# design.net
KiCad netlist of a schematic drawn in Altium Designer
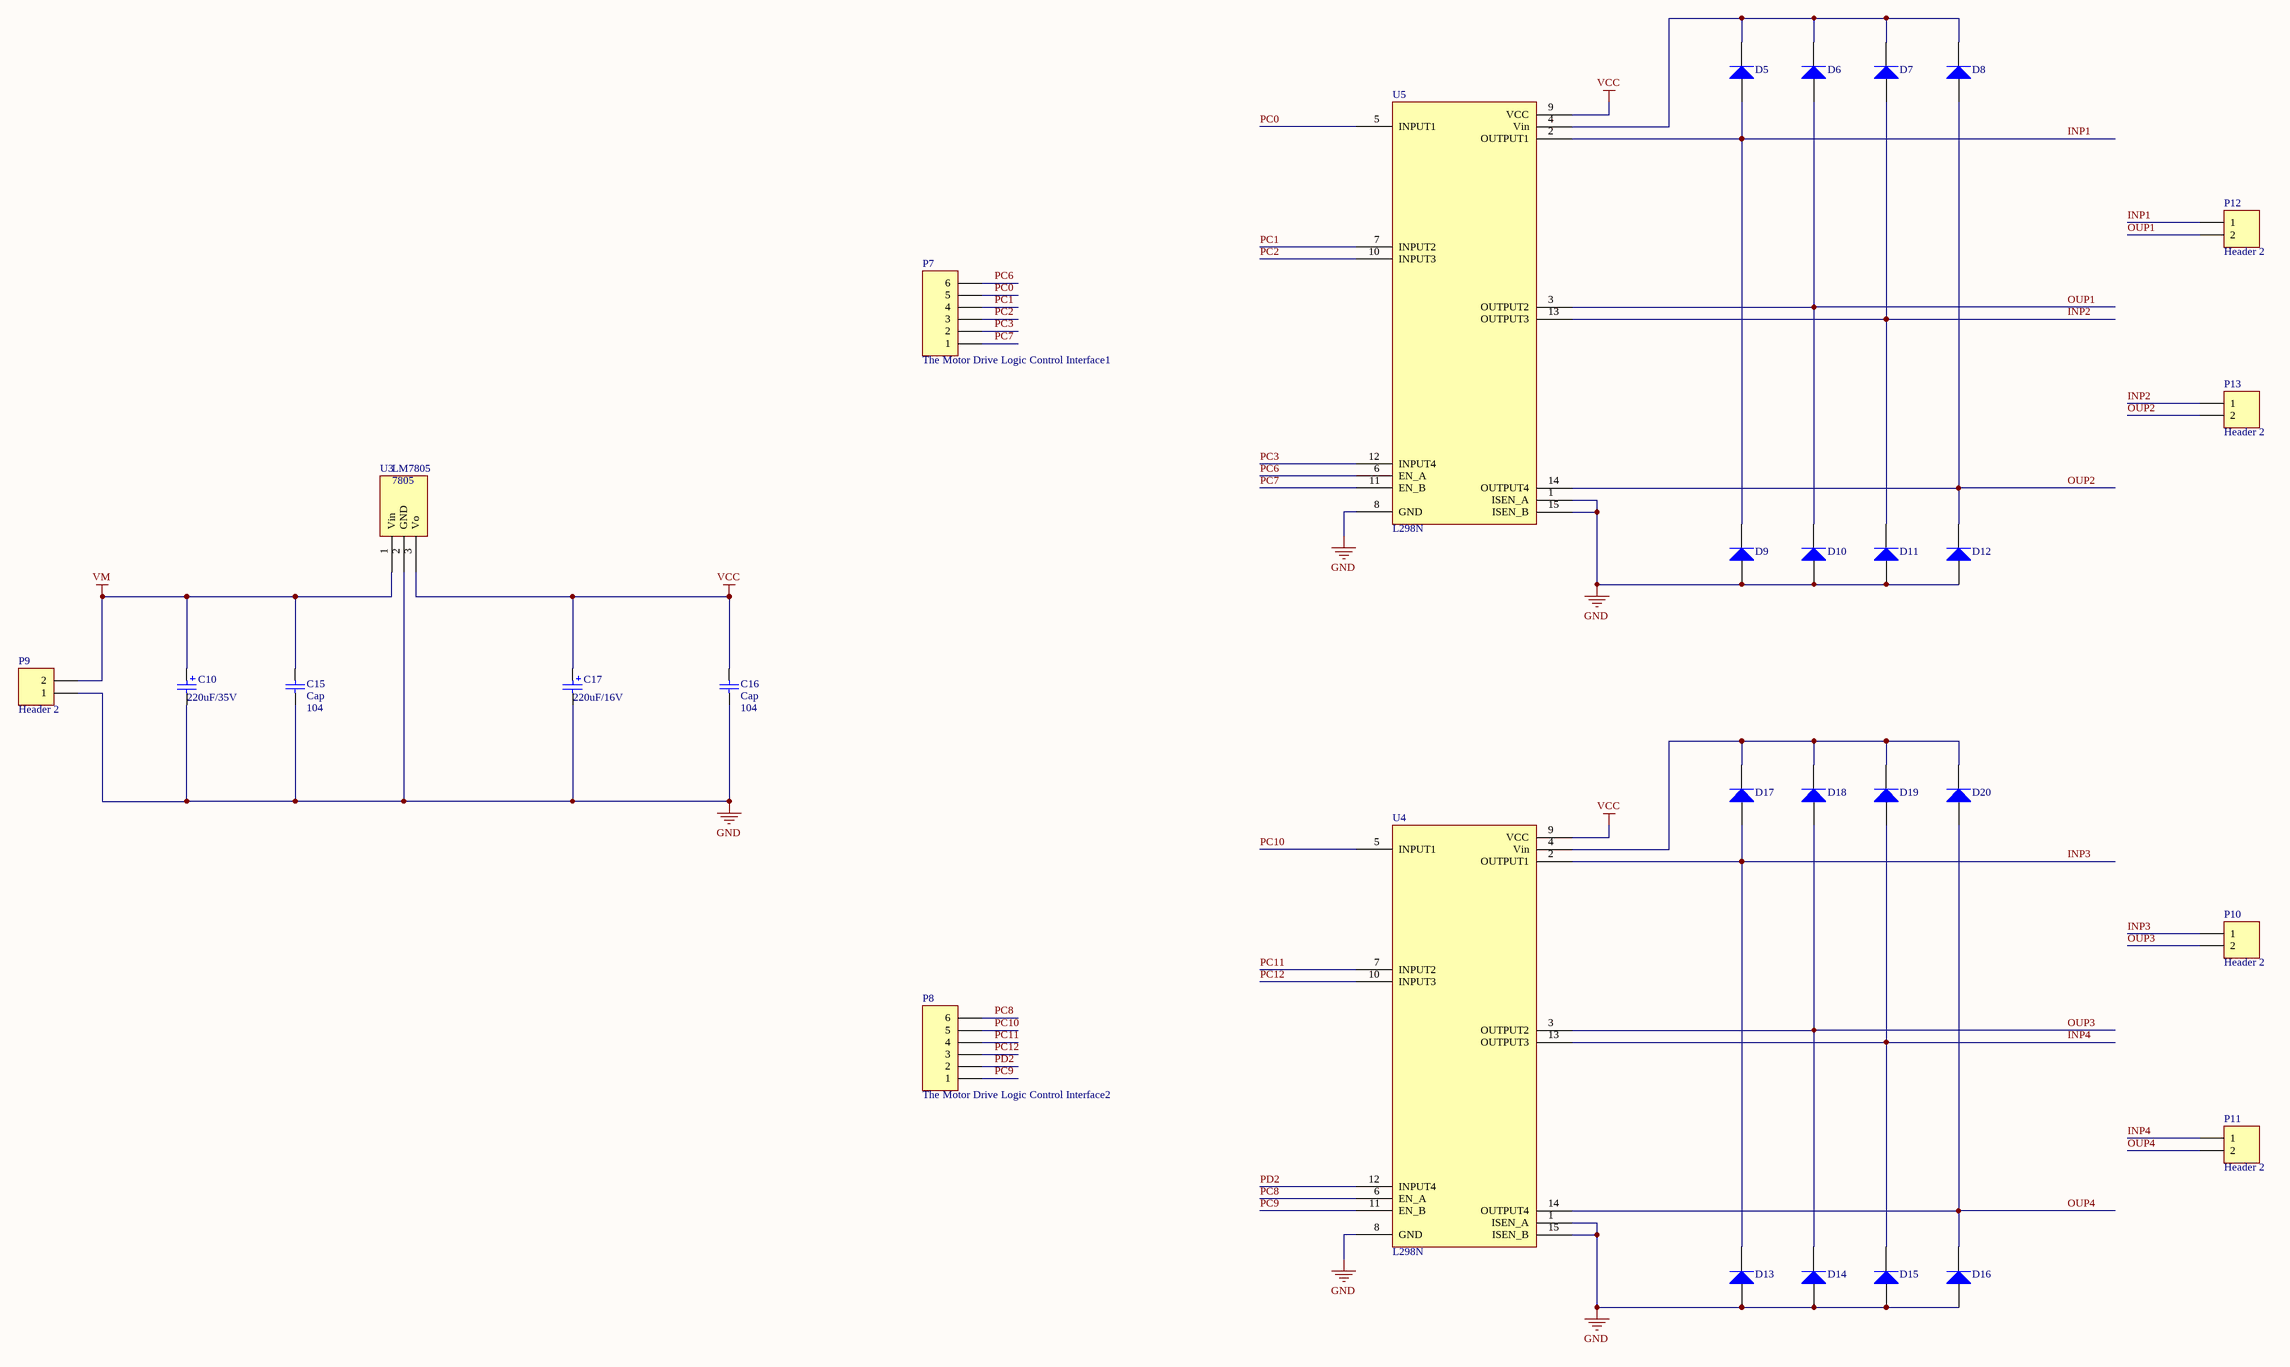
[diagram p0: 嵌入式驱动模块.SchDoc]

(export (version "E")
  (design (tool "Eeschema 10.0.6"))
  (components
    (comp (ref "C10")
      (value "220uF/35V")
      (footprint "RB 5/10")
      (description "Polarized Capacitor (Axial)")
      (fields (field (name "Comment") "Cap Pol2") (field (name "PUBLISHER") "Altium Limited"))
      (libsource (lib "Miscellaneous Devices") (part "Cap Pol2"))
    )
    (comp (ref "C15")
      (value "Cap")
      (footprint "CAP-0.1")
      (description "Capacitor")
      (fields (field (name "ALTIUM_VALUE") "104") (field (name "PUBLISHER") "Altium Limited"))
      (libsource (lib "Miscellaneous Devices") (part "Cap"))
    )
    (comp (ref "C16")
      (value "Cap")
      (footprint "CAP-0.1")
      (description "Capacitor")
      (fields (field (name "ALTIUM_VALUE") "104") (field (name "PUBLISHER") "Altium Limited"))
      (libsource (lib "Miscellaneous Devices") (part "Cap"))
    )
    (comp (ref "C17")
      (value "220uF/16V")
      (footprint "RB 5/10")
      (description "Polarized Capacitor (Axial)")
      (fields (field (name "Comment") "Cap Pol2") (field (name "PUBLISHER") "Altium Limited"))
      (libsource (lib "Miscellaneous Devices") (part "Cap Pol2"))
    )
    (comp (ref "D5")
      (value "~")
      (footprint "DO-41")
      (description "High Conductance Fast Diode")
      (fields (field (name "PUBLISHER") "Altium Limited"))
      (libsource (lib "Miscellaneous Devices") (part "Diode 1N914"))
    )
    (comp (ref "D6")
      (value "Diode 1N914")
      (footprint "DO-41")
      (description "High Conductance Fast Diode")
      (fields (field (name "PUBLISHER") "Altium Limited"))
      (libsource (lib "Miscellaneous Devices") (part "Diode 1N914"))
    )
    (comp (ref "D7")
      (value "Diode 1N914")
      (footprint "DO-41")
      (description "High Conductance Fast Diode")
      (fields (field (name "PUBLISHER") "Altium Limited"))
      (libsource (lib "Miscellaneous Devices") (part "Diode 1N914"))
    )
    (comp (ref "D8")
      (value "~")
      (footprint "DO-41")
      (description "High Conductance Fast Diode")
      (fields (field (name "PUBLISHER") "Altium Limited"))
      (libsource (lib "Miscellaneous Devices") (part "Diode 1N914"))
    )
    (comp (ref "D9")
      (value "Diode 1N914")
      (footprint "DO-41")
      (description "High Conductance Fast Diode")
      (fields (field (name "PUBLISHER") "Altium Limited"))
      (libsource (lib "Miscellaneous Devices") (part "Diode 1N914"))
    )
    (comp (ref "D10")
      (value "Diode 1N914")
      (footprint "DO-41")
      (description "High Conductance Fast Diode")
      (fields (field (name "PUBLISHER") "Altium Limited"))
      (libsource (lib "Miscellaneous Devices") (part "Diode 1N914"))
    )
    (comp (ref "D11")
      (value "Diode 1N914")
      (footprint "DO-41")
      (description "High Conductance Fast Diode")
      (fields (field (name "PUBLISHER") "Altium Limited"))
      (libsource (lib "Miscellaneous Devices") (part "Diode 1N914"))
    )
    (comp (ref "D12")
      (value "Diode 1N914")
      (footprint "DO-41")
      (description "High Conductance Fast Diode")
      (fields (field (name "PUBLISHER") "Altium Limited"))
      (libsource (lib "Miscellaneous Devices") (part "Diode 1N914"))
    )
    (comp (ref "D13")
      (value "Diode 1N914")
      (footprint "DO-41")
      (description "High Conductance Fast Diode")
      (fields (field (name "PUBLISHER") "Altium Limited"))
      (libsource (lib "Miscellaneous Devices") (part "Diode 1N914"))
    )
    (comp (ref "D14")
      (value "Diode 1N914")
      (footprint "DO-41")
      (description "High Conductance Fast Diode")
      (fields (field (name "PUBLISHER") "Altium Limited"))
      (libsource (lib "Miscellaneous Devices") (part "Diode 1N914"))
    )
    (comp (ref "D15")
      (value "Diode 1N914")
      (footprint "DO-41")
      (description "High Conductance Fast Diode")
      (fields (field (name "PUBLISHER") "Altium Limited"))
      (libsource (lib "Miscellaneous Devices") (part "Diode 1N914"))
    )
    (comp (ref "D16")
      (value "Diode 1N914")
      (footprint "DO-41")
      (description "High Conductance Fast Diode")
      (fields (field (name "PUBLISHER") "Altium Limited"))
      (libsource (lib "Miscellaneous Devices") (part "Diode 1N914"))
    )
    (comp (ref "D17")
      (value "~")
      (footprint "DO-41")
      (description "High Conductance Fast Diode")
      (fields (field (name "PUBLISHER") "Altium Limited"))
      (libsource (lib "Miscellaneous Devices") (part "Diode 1N914"))
    )
    (comp (ref "D18")
      (value "Diode 1N914")
      (footprint "DO-41")
      (description "High Conductance Fast Diode")
      (fields (field (name "PUBLISHER") "Altium Limited"))
      (libsource (lib "Miscellaneous Devices") (part "Diode 1N914"))
    )
    (comp (ref "D19")
      (value "Diode 1N914")
      (footprint "DO-41")
      (description "High Conductance Fast Diode")
      (fields (field (name "PUBLISHER") "Altium Limited"))
      (libsource (lib "Miscellaneous Devices") (part "Diode 1N914"))
    )
    (comp (ref "D20")
      (value "~")
      (footprint "DO-41")
      (description "High Conductance Fast Diode")
      (fields (field (name "PUBLISHER") "Altium Limited"))
      (libsource (lib "Miscellaneous Devices") (part "Diode 1N914"))
    )
    (comp (ref "P7")
      (value "The Motor Drive Logic Control Interface1")
      (footprint "HDR-1X6")
      (description "Header, 6-Pin")
      (fields (field (name "PUBLISHER") "Altium Limited"))
      (libsource (lib "Miscellaneous Connectors") (part "Header 6"))
    )
    (comp (ref "P8")
      (value "The Motor Drive Logic Control Interface2")
      (footprint "HDR-1X6")
      (description "Header, 6-Pin")
      (fields (field (name "PUBLISHER") "Altium Limited"))
      (libsource (lib "Miscellaneous Connectors") (part "Header 6"))
    )
    (comp (ref "P9")
      (value "Header 2")
      (footprint "KF301-2P")
      (description "Header, 2-Pin")
      (fields (field (name "PUBLISHER") "Altium Limited"))
      (libsource (lib "") (part "Header 2_1"))
    )
    (comp (ref "P10")
      (value "Header 2")
      (footprint "KF301-2P")
      (description "Header, 2-Pin")
      (fields (field (name "PUBLISHER") "Altium Limited"))
      (libsource (lib "Miscellaneous Connectors") (part "Header 2"))
    )
    (comp (ref "P11")
      (value "Header 2")
      (footprint "KF301-2P")
      (description "Header, 2-Pin")
      (fields (field (name "PUBLISHER") "Altium Limited"))
      (libsource (lib "Miscellaneous Connectors") (part "Header 2"))
    )
    (comp (ref "P12")
      (value "Header 2")
      (footprint "KF301-2P")
      (description "Header, 2-Pin")
      (fields (field (name "PUBLISHER") "Altium Limited"))
      (libsource (lib "Miscellaneous Connectors") (part "Header 2"))
    )
    (comp (ref "P13")
      (value "Header 2")
      (footprint "KF301-2P")
      (description "Header, 2-Pin")
      (fields (field (name "PUBLISHER") "Altium Limited"))
      (libsource (lib "Miscellaneous Connectors") (part "Header 2"))
    )
    (comp (ref "U3")
      (value "LM7805")
      (footprint "TO-220(TO-220-3)")
      (libsource (lib "Schlib6") (part "Component_1"))
    )
    (comp (ref "U4") (value "L298N") (footprint "L298") (libsource (lib "Schlib2") (part "Component_1")))
    (comp (ref "U5") (value "L298N") (footprint "L298") (libsource (lib "Schlib2") (part "Component_1")))
  )
  (nets
    (net (code "1") (name "/INP1") (class "Default")
      (node (ref "D5") (pin "1") (pinfunction "A_1") (pintype "passive"))
      (node (ref "D9") (pin "2") (pinfunction "K_2") (pintype "passive"))
      (node (ref "P12") (pin "1") (pinfunction "1_1") (pintype "passive"))
      (node (ref "U5") (pin "2") (pinfunction "OUTPUT1_2") (pintype "passive"))
    )
    (net (code "2") (name "/INP2") (class "Default")
      (node (ref "D11") (pin "2") (pinfunction "K_2") (pintype "passive"))
      (node (ref "D7") (pin "1") (pinfunction "A_1") (pintype "passive"))
      (node (ref "P13") (pin "1") (pinfunction "1_1") (pintype "passive"))
      (node (ref "U5") (pin "13") (pinfunction "OUTPUT3_13") (pintype "passive"))
    )
    (net (code "3") (name "/INP3") (class "Default")
      (node (ref "D13") (pin "2") (pinfunction "K_2") (pintype "passive"))
      (node (ref "D17") (pin "1") (pinfunction "A_1") (pintype "passive"))
      (node (ref "P10") (pin "1") (pinfunction "1_1") (pintype "passive"))
      (node (ref "U4") (pin "2") (pinfunction "OUTPUT1_2") (pintype "passive"))
    )
    (net (code "4") (name "/INP4") (class "Default")
      (node (ref "D15") (pin "2") (pinfunction "K_2") (pintype "passive"))
      (node (ref "D19") (pin "1") (pinfunction "A_1") (pintype "passive"))
      (node (ref "P11") (pin "1") (pinfunction "1_1") (pintype "passive"))
      (node (ref "U4") (pin "13") (pinfunction "OUTPUT3_13") (pintype "passive"))
    )
    (net (code "5") (name "/OUP1") (class "Default")
      (node (ref "D10") (pin "2") (pinfunction "K_2") (pintype "passive"))
      (node (ref "D6") (pin "1") (pinfunction "A_1") (pintype "passive"))
      (node (ref "P12") (pin "2") (pinfunction "2_2") (pintype "passive"))
      (node (ref "U5") (pin "3") (pinfunction "OUTPUT2_3") (pintype "passive"))
    )
    (net (code "6") (name "/OUP2") (class "Default")
      (node (ref "D12") (pin "2") (pinfunction "K_2") (pintype "passive"))
      (node (ref "D8") (pin "1") (pinfunction "A_1") (pintype "passive"))
      (node (ref "P13") (pin "2") (pinfunction "2_2") (pintype "passive"))
      (node (ref "U5") (pin "14") (pinfunction "OUTPUT4_14") (pintype "passive"))
    )
    (net (code "7") (name "/OUP3") (class "Default")
      (node (ref "D14") (pin "2") (pinfunction "K_2") (pintype "passive"))
      (node (ref "D18") (pin "1") (pinfunction "A_1") (pintype "passive"))
      (node (ref "P10") (pin "2") (pinfunction "2_2") (pintype "passive"))
      (node (ref "U4") (pin "3") (pinfunction "OUTPUT2_3") (pintype "passive"))
    )
    (net (code "8") (name "/OUP4") (class "Default")
      (node (ref "D16") (pin "2") (pinfunction "K_2") (pintype "passive"))
      (node (ref "D20") (pin "1") (pinfunction "A_1") (pintype "passive"))
      (node (ref "P11") (pin "2") (pinfunction "2_2") (pintype "passive"))
      (node (ref "U4") (pin "14") (pinfunction "OUTPUT4_14") (pintype "passive"))
    )
    (net (code "9") (name "/PC0") (class "Default")
      (node (ref "P7") (pin "5") (pinfunction "5_5") (pintype "passive"))
      (node (ref "U5") (pin "5") (pinfunction "INPUT1_5") (pintype "passive"))
    )
    (net (code "10") (name "/PC1") (class "Default")
      (node (ref "P7") (pin "4") (pinfunction "4_4") (pintype "passive"))
      (node (ref "U5") (pin "7") (pinfunction "INPUT2_7") (pintype "passive"))
    )
    (net (code "11") (name "/PC2") (class "Default")
      (node (ref "P7") (pin "3") (pinfunction "3_3") (pintype "passive"))
      (node (ref "U5") (pin "10") (pinfunction "INPUT3_10") (pintype "passive"))
    )
    (net (code "12") (name "/PC3") (class "Default")
      (node (ref "P7") (pin "2") (pinfunction "2_2") (pintype "passive"))
      (node (ref "U5") (pin "12") (pinfunction "INPUT4_12") (pintype "passive"))
    )
    (net (code "13") (name "/PC6") (class "Default")
      (node (ref "P7") (pin "6") (pinfunction "6_6") (pintype "passive"))
      (node (ref "U5") (pin "6") (pinfunction "EN_A_6") (pintype "passive"))
    )
    (net (code "14") (name "/PC7") (class "Default")
      (node (ref "P7") (pin "1") (pinfunction "1_1") (pintype "passive"))
      (node (ref "U5") (pin "11") (pinfunction "EN_B_11") (pintype "passive"))
    )
    (net (code "15") (name "/PC8") (class "Default")
      (node (ref "P8") (pin "6") (pinfunction "6_6") (pintype "passive"))
      (node (ref "U4") (pin "6") (pinfunction "EN_A_6") (pintype "passive"))
    )
    (net (code "16") (name "/PC9") (class "Default")
      (node (ref "P8") (pin "1") (pinfunction "1_1") (pintype "passive"))
      (node (ref "U4") (pin "11") (pinfunction "EN_B_11") (pintype "passive"))
    )
    (net (code "17") (name "/PC10") (class "Default")
      (node (ref "P8") (pin "5") (pinfunction "5_5") (pintype "passive"))
      (node (ref "U4") (pin "5") (pinfunction "INPUT1_5") (pintype "passive"))
    )
    (net (code "18") (name "/PC11") (class "Default")
      (node (ref "P8") (pin "4") (pinfunction "4_4") (pintype "passive"))
      (node (ref "U4") (pin "7") (pinfunction "INPUT2_7") (pintype "passive"))
    )
    (net (code "19") (name "/PC12") (class "Default")
      (node (ref "P8") (pin "3") (pinfunction "3_3") (pintype "passive"))
      (node (ref "U4") (pin "10") (pinfunction "INPUT3_10") (pintype "passive"))
    )
    (net (code "20") (name "/PD2") (class "Default")
      (node (ref "P8") (pin "2") (pinfunction "2_2") (pintype "passive"))
      (node (ref "U4") (pin "12") (pinfunction "INPUT4_12") (pintype "passive"))
    )
    (net (code "21") (name "GND") (class "Default")
      (node (ref "C10") (pin "2") (pinfunction "2_2") (pintype "passive"))
      (node (ref "C15") (pin "1") (pinfunction "1_1") (pintype "passive"))
      (node (ref "C16") (pin "1") (pinfunction "1_1") (pintype "passive"))
      (node (ref "C17") (pin "2") (pinfunction "2_2") (pintype "passive"))
      (node (ref "D10") (pin "1") (pinfunction "A_1") (pintype "passive"))
      (node (ref "D11") (pin "1") (pinfunction "A_1") (pintype "passive"))
      (node (ref "D12") (pin "1") (pinfunction "A_1") (pintype "passive"))
      (node (ref "D13") (pin "1") (pinfunction "A_1") (pintype "passive"))
      (node (ref "D14") (pin "1") (pinfunction "A_1") (pintype "passive"))
      (node (ref "D15") (pin "1") (pinfunction "A_1") (pintype "passive"))
      (node (ref "D16") (pin "1") (pinfunction "A_1") (pintype "passive"))
      (node (ref "D9") (pin "1") (pinfunction "A_1") (pintype "passive"))
      (node (ref "P9") (pin "1") (pinfunction "1_1") (pintype "passive"))
      (node (ref "U3") (pin "2") (pinfunction "GND_2") (pintype "passive"))
      (node (ref "U4") (pin "1") (pinfunction "ISEN_A_1") (pintype "passive"))
      (node (ref "U4") (pin "15") (pinfunction "ISEN_B_15") (pintype "passive"))
      (node (ref "U4") (pin "8") (pinfunction "GND_8") (pintype "passive"))
      (node (ref "U5") (pin "1") (pinfunction "ISEN_A_1") (pintype "passive"))
      (node (ref "U5") (pin "15") (pinfunction "ISEN_B_15") (pintype "passive"))
      (node (ref "U5") (pin "8") (pinfunction "GND_8") (pintype "passive"))
    )
    (net (code "22") (name "Net-(D5-K)") (class "Default")
      (node (ref "D5") (pin "2") (pinfunction "K_2") (pintype "passive"))
      (node (ref "D6") (pin "2") (pinfunction "K_2") (pintype "passive"))
      (node (ref "D7") (pin "2") (pinfunction "K_2") (pintype "passive"))
      (node (ref "D8") (pin "2") (pinfunction "K_2") (pintype "passive"))
      (node (ref "U5") (pin "4") (pinfunction "Vin_4") (pintype "passive"))
    )
    (net (code "23") (name "Net-(D17-K)") (class "Default")
      (node (ref "D17") (pin "2") (pinfunction "K_2") (pintype "passive"))
      (node (ref "D18") (pin "2") (pinfunction "K_2") (pintype "passive"))
      (node (ref "D19") (pin "2") (pinfunction "K_2") (pintype "passive"))
      (node (ref "D20") (pin "2") (pinfunction "K_2") (pintype "passive"))
      (node (ref "U4") (pin "4") (pinfunction "Vin_4") (pintype "passive"))
    )
    (net (code "24") (name "VCC") (class "Default")
      (node (ref "C16") (pin "2") (pinfunction "2_2") (pintype "passive"))
      (node (ref "C17") (pin "1") (pinfunction "1_1") (pintype "passive"))
      (node (ref "U3") (pin "3") (pinfunction "Vo_3") (pintype "passive"))
      (node (ref "U4") (pin "9") (pinfunction "VCC_9") (pintype "passive"))
      (node (ref "U5") (pin "9") (pinfunction "VCC_9") (pintype "passive"))
    )
    (net (code "25") (name "VM") (class "Default")
      (node (ref "C10") (pin "1") (pinfunction "1_1") (pintype "passive"))
      (node (ref "C15") (pin "2") (pinfunction "2_2") (pintype "passive"))
      (node (ref "P9") (pin "2") (pinfunction "2_2") (pintype "passive"))
      (node (ref "U3") (pin "1") (pinfunction "Vin_1") (pintype "passive"))
    )
  )
)
